# drvinput4.net
KiCad netlist of a schematic drawn in Altium Designer
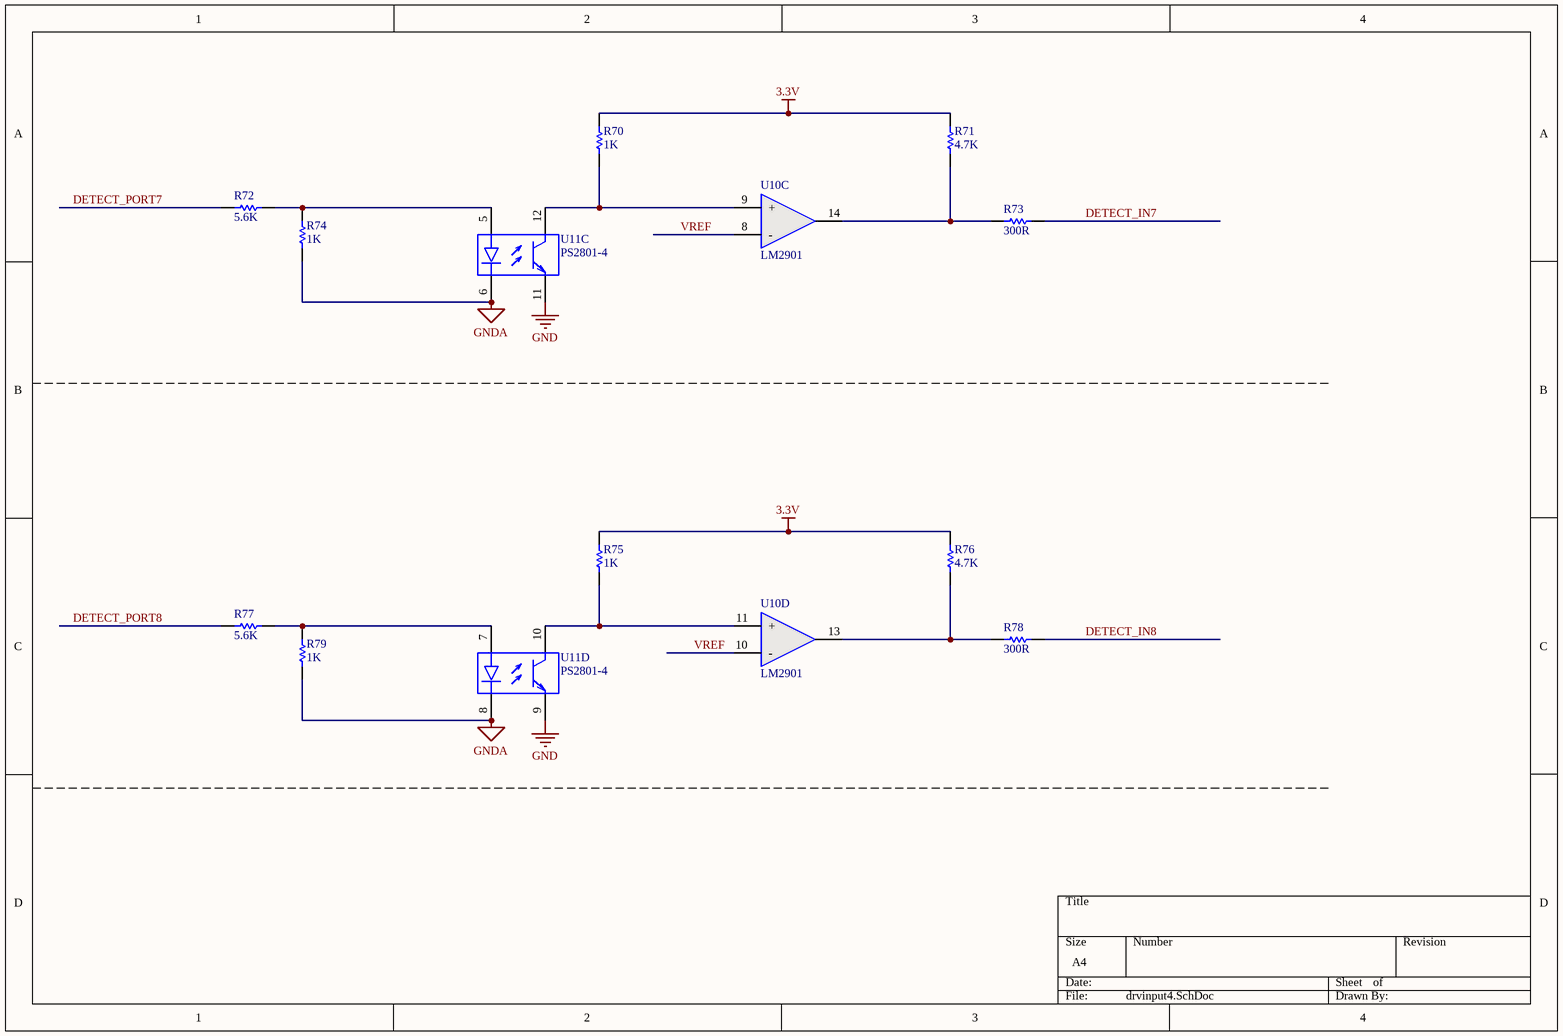
[diagram p0: drvinput4.SchDoc]

(export (version "E")
  (design (tool "Eeschema 10.0.6"))
  (components
    (comp (ref "R70")
      (value "1K")
      (footprint "RESC2012M")
      (description "Resistor")
      (fields (field (name "PUBLISHER") "Altium Limited"))
      (libsource (lib "Miscellaneous Devices") (part "Res1"))
    )
    (comp (ref "R71")
      (value "4.7K")
      (footprint "RESC2012M")
      (description "Resistor")
      (fields (field (name "PUBLISHER") "Altium Limited"))
      (libsource (lib "Miscellaneous Devices") (part "Res1"))
    )
    (comp (ref "R72")
      (value "5.6K")
      (footprint "RESC2012M")
      (description "Resistor")
      (fields (field (name "PUBLISHER") "Altium Limited"))
      (libsource (lib "Miscellaneous Devices") (part "Res1"))
    )
    (comp (ref "R73")
      (value "300R")
      (footprint "RESC2012M")
      (description "Resistor")
      (fields (field (name "PUBLISHER") "Altium Limited"))
      (libsource (lib "Miscellaneous Devices") (part "Res1"))
    )
    (comp (ref "R74")
      (value "1K")
      (footprint "RESC2012M")
      (description "Resistor")
      (fields (field (name "PUBLISHER") "Altium Limited"))
      (libsource (lib "Miscellaneous Devices") (part "Res1"))
    )
    (comp (ref "R75")
      (value "1K")
      (footprint "RESC2012M")
      (description "Resistor")
      (fields (field (name "PUBLISHER") "Altium Limited"))
      (libsource (lib "Miscellaneous Devices") (part "Res1"))
    )
    (comp (ref "R76")
      (value "4.7K")
      (footprint "RESC2012M")
      (description "Resistor")
      (fields (field (name "PUBLISHER") "Altium Limited"))
      (libsource (lib "Miscellaneous Devices") (part "Res1"))
    )
    (comp (ref "R77")
      (value "5.6K")
      (footprint "RESC2012M")
      (description "Resistor")
      (fields (field (name "PUBLISHER") "Altium Limited"))
      (libsource (lib "Miscellaneous Devices") (part "Res1"))
    )
    (comp (ref "R78")
      (value "300R")
      (footprint "RESC2012M")
      (description "Resistor")
      (fields (field (name "PUBLISHER") "Altium Limited"))
      (libsource (lib "Miscellaneous Devices") (part "Res1"))
    )
    (comp (ref "R79")
      (value "1K")
      (footprint "RESC2012M")
      (description "Resistor")
      (fields (field (name "PUBLISHER") "Altium Limited"))
      (libsource (lib "Miscellaneous Devices") (part "Res1"))
    )
    (comp (ref "U10")
      (value "LM2901")
      (footprint "SOIC-14AM")
      (description "4通道差分比较器芯片")
      (libsource (lib "UserSchDev") (part "LM2901"))
    )
    (comp (ref "U11")
      (value "PS2801-4")
      (footprint "SOIC16_N")
      (fields (field (name "PUBLISHER") "Altium Limited"))
      (libsource (lib "UserSchDev") (part "PS2801-4"))
    )
  )
  (nets
    (net (code "1") (name "/DETECT_IN7") (class "Default")
      (node (ref "R73") (pin "1") (pinfunction "1_1") (pintype "passive"))
    )
    (net (code "2") (name "/DETECT_IN8") (class "Default")
      (node (ref "R78") (pin "2") (pinfunction "2_2") (pintype "passive"))
    )
    (net (code "3") (name "/DETECT_PORT7") (class "Default")
      (node (ref "R72") (pin "2") (pinfunction "2_2") (pintype "passive"))
    )
    (net (code "4") (name "/DETECT_PORT8") (class "Default")
      (node (ref "R77") (pin "2") (pinfunction "2_2") (pintype "passive"))
    )
    (net (code "5") (name "/VREF") (class "Default")
      (node (ref "U10") (pin "10") (pinfunction "-_10") (pintype "passive"))
      (node (ref "U10") (pin "8") (pinfunction "-_8") (pintype "passive"))
    )
    (net (code "6") (name "3.3V") (class "Default")
      (node (ref "R70") (pin "1") (pinfunction "1_1") (pintype "passive"))
      (node (ref "R71") (pin "2") (pinfunction "2_2") (pintype "passive"))
      (node (ref "R75") (pin "1") (pinfunction "1_1") (pintype "passive"))
      (node (ref "R76") (pin "2") (pinfunction "2_2") (pintype "passive"))
    )
    (net (code "7") (name "GND") (class "Default")
      (node (ref "U11") (pin "11") (pinfunction "E_11") (pintype "passive"))
      (node (ref "U11") (pin "9") (pinfunction "E_9") (pintype "passive"))
    )
    (net (code "8") (name "GNDA") (class "Default")
      (node (ref "R74") (pin "1") (pinfunction "1_1") (pintype "passive"))
      (node (ref "R79") (pin "1") (pinfunction "1_1") (pintype "passive"))
      (node (ref "U11") (pin "6") (pinfunction "-_6") (pintype "passive"))
      (node (ref "U11") (pin "8") (pinfunction "-_8") (pintype "passive"))
    )
    (net (code "9") (name "Net-(U10C-+)") (class "Default")
      (node (ref "R70") (pin "2") (pinfunction "2_2") (pintype "passive"))
      (node (ref "U10") (pin "9") (pinfunction "+_9") (pintype "passive"))
      (node (ref "U11") (pin "12") (pinfunction "C_12") (pintype "passive"))
    )
    (net (code "10") (name "Net-(U10C-OUT)") (class "Default")
      (node (ref "R71") (pin "1") (pinfunction "1_1") (pintype "passive"))
      (node (ref "R73") (pin "2") (pinfunction "2_2") (pintype "passive"))
      (node (ref "U10") (pin "14") (pinfunction "OUT_14") (pintype "passive"))
    )
    (net (code "11") (name "Net-(U10D-+)") (class "Default")
      (node (ref "R75") (pin "2") (pinfunction "2_2") (pintype "passive"))
      (node (ref "U10") (pin "11") (pinfunction "+_11") (pintype "passive"))
      (node (ref "U11") (pin "10") (pinfunction "C_10") (pintype "passive"))
    )
    (net (code "12") (name "Net-(U10D-OUT)") (class "Default")
      (node (ref "R76") (pin "1") (pinfunction "1_1") (pintype "passive"))
      (node (ref "R78") (pin "1") (pinfunction "1_1") (pintype "passive"))
      (node (ref "U10") (pin "13") (pinfunction "OUT_13") (pintype "passive"))
    )
    (net (code "13") (name "Net-(U11C-+)") (class "Default")
      (node (ref "R72") (pin "1") (pinfunction "1_1") (pintype "passive"))
      (node (ref "R74") (pin "2") (pinfunction "2_2") (pintype "passive"))
      (node (ref "U11") (pin "5") (pinfunction "+_5") (pintype "passive"))
    )
    (net (code "14") (name "Net-(U11D-+)") (class "Default")
      (node (ref "R77") (pin "1") (pinfunction "1_1") (pintype "passive"))
      (node (ref "R79") (pin "2") (pinfunction "2_2") (pintype "passive"))
      (node (ref "U11") (pin "7") (pinfunction "+_7") (pintype "passive"))
    )
  )
)
